# Minimal_carrier_board_for_CM4_rev_A.net
KiCad netlist of a schematic drawn in EAGLE
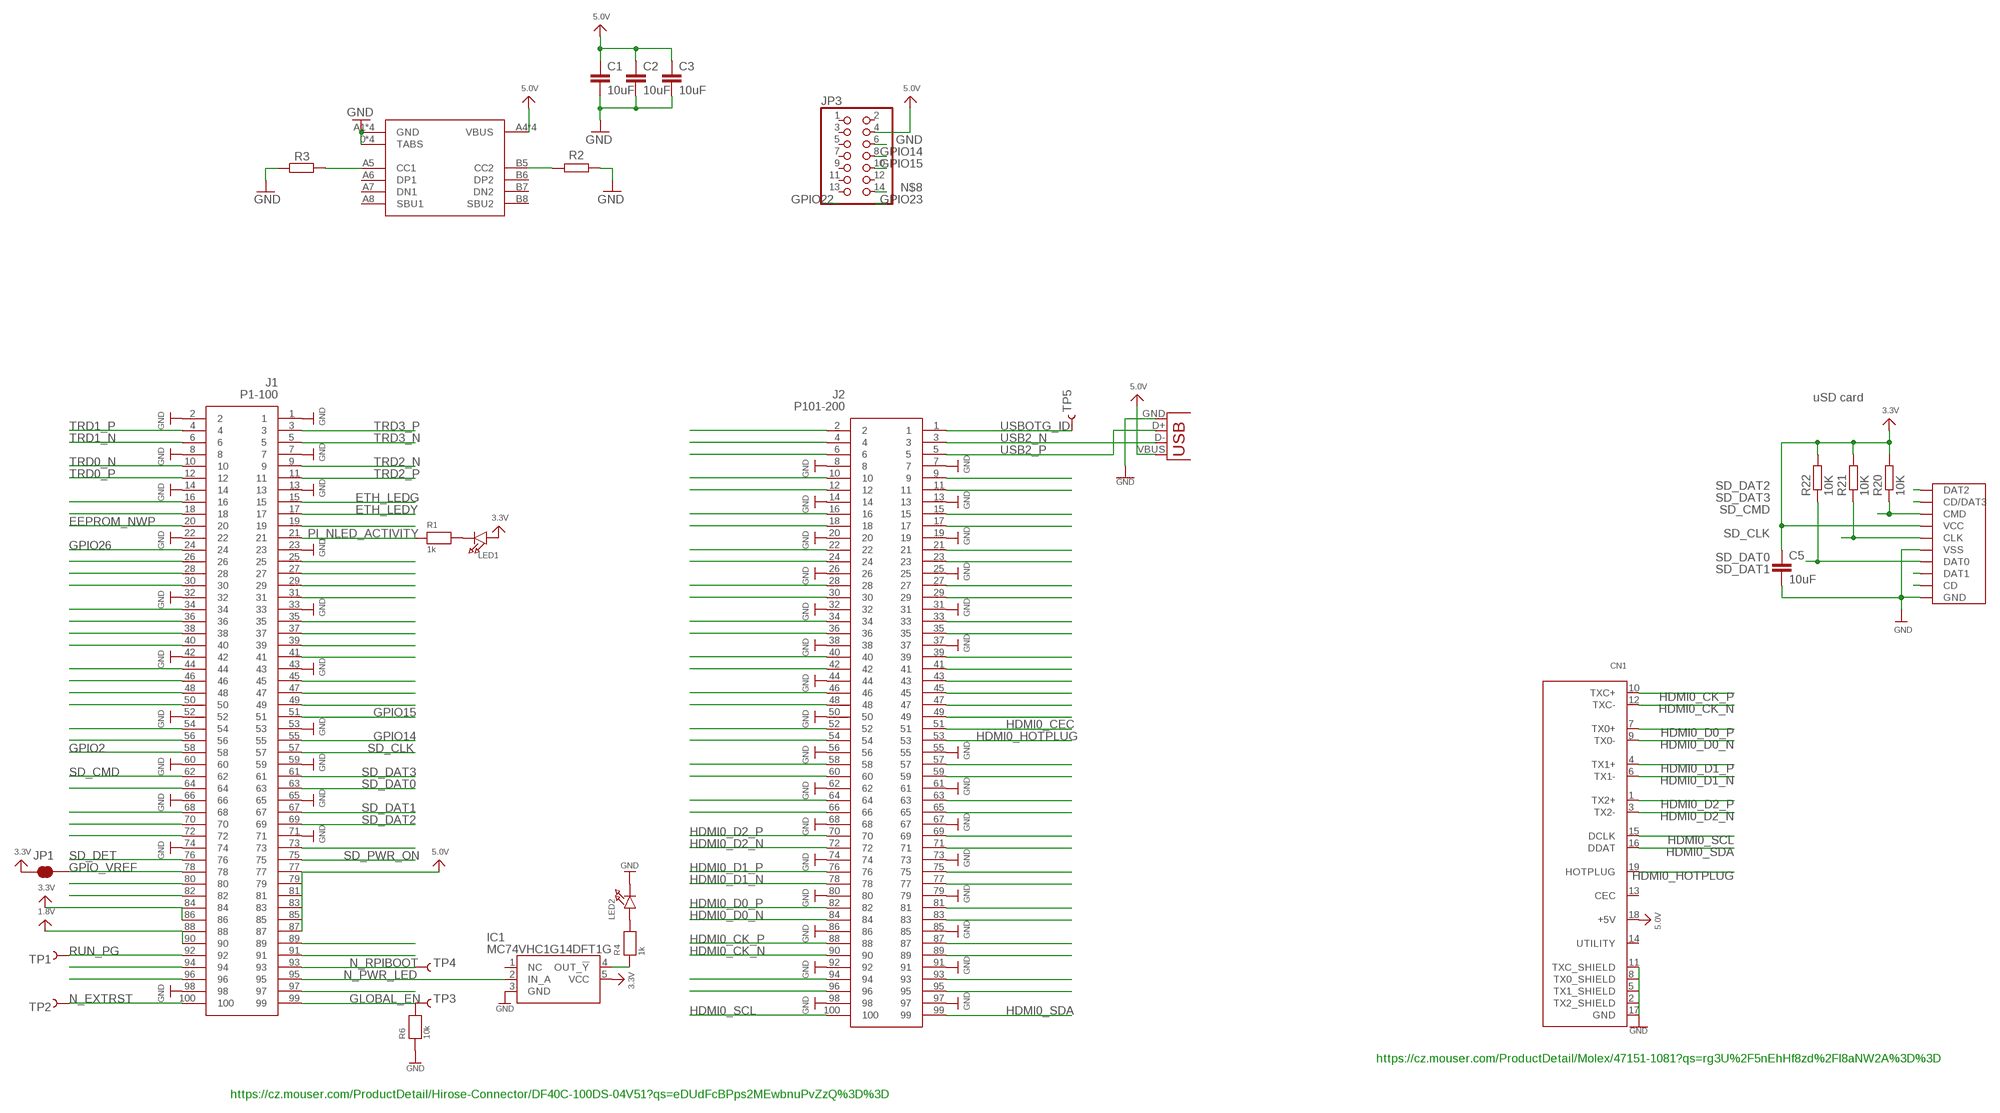
[diagram p0: schematic, sheet 1]

(export (version "E")
  (design (tool "Eeschema 10.0.6"))
  (components
    (comp (ref "C1")
      (value "10uF")
      (footprint "eagle-import:C0805")
      (libsource (lib "eagle-import") (part "C-EUC0805"))
    )
    (comp (ref "C2")
      (value "10uF")
      (footprint "eagle-import:C0805")
      (libsource (lib "eagle-import") (part "C-EUC0805"))
    )
    (comp (ref "C3")
      (value "10uF")
      (footprint "eagle-import:C0805")
      (libsource (lib "eagle-import") (part "C-EUC0805"))
    )
    (comp (ref "C5")
      (value "10uF")
      (footprint "eagle-import:C0805")
      (libsource (lib "eagle-import") (part "C-EUC0805"))
    )
    (comp (ref "CN1")
      (value "HDMI_MOLEX_47151-0001")
      (footprint "eagle-import:HDMI_MOLEX_47151-0001")
      (libsource (lib "eagle-import") (part "HDMI_MOLEX_47151-0001"))
    )
    (comp (ref "IC1")
      (value "MC74VHC1G14DFT1G")
      (footprint "eagle-import:SOT65P210X110-5N")
      (fields (field (name "MOUSER_PART_NUMBER") "863-MC74VHC1G14DFT1G"))
      (libsource (lib "eagle-import") (part "MC74VHC1G14DFT1G"))
    )
    (comp (ref "J1")
      (value "P1-100")
      (footprint "eagle-import:DF40C100DS04V51")
      (fields
        (field (name "MANUFACTURER_PART_NUMBER") "DF40C-100DS-0.4V(51)")
        (field (name "MOUSER_PART_NUMBER") "798-DF40C100DS0.4V51")
      )
      (libsource (lib "eagle-import") (part "DF40C-100DS-0.4V_51_"))
    )
    (comp (ref "J2")
      (value "P101-200")
      (footprint "eagle-import:DF40C100DS04V51")
      (fields
        (field (name "MANUFACTURER_PART_NUMBER") "DF40C-100DS-0.4V(51)")
        (field (name "MOUSER_PART_NUMBER") "798-DF40C100DS0.4V51")
      )
      (libsource (lib "eagle-import") (part "DF40C-100DS-0.4V_51_"))
    )
    (comp (ref "JP1")
      (value "JUMPER-SMT_2_NC_TRACE_NO-SILK")
      (footprint "eagle-import:SMT-JUMPER_2_NC_TRACE_NO-SILK")
      (libsource (lib "eagle-import") (part "JUMPER-SMT_2_NC_TRACE_NO-SILK"))
    )
    (comp (ref "JP3")
      (value "PINHD-2X7")
      (footprint "eagle-import:2X07")
      (libsource (lib "eagle-import") (part "PINHD-2X7"))
    )
    (comp (ref "LED1")
      (value "LED0805_NOOUTLINE")
      (footprint "eagle-import:CHIPLED_0805_NOOUTLINE")
      (libsource (lib "eagle-import") (part "LED0805_NOOUTLINE"))
    )
    (comp (ref "LED2")
      (value "LED0805_NOOUTLINE")
      (footprint "eagle-import:CHIPLED_0805_NOOUTLINE")
      (libsource (lib "eagle-import") (part "LED0805_NOOUTLINE"))
    )
    (comp (ref "R1")
      (value "1k")
      (footprint "eagle-import:_0805MP")
      (libsource (lib "eagle-import") (part "RESISTOR_0805MP"))
    )
    (comp (ref "R2")
      (value "5.1k")
      (footprint "eagle-import:R0805")
      (libsource (lib "eagle-import") (part "R-EU_R0805"))
    )
    (comp (ref "R3")
      (value "5.1k")
      (footprint "eagle-import:R0805")
      (libsource (lib "eagle-import") (part "R-EU_R0805"))
    )
    (comp (ref "R4")
      (value "1k")
      (footprint "eagle-import:_0805MP")
      (libsource (lib "eagle-import") (part "RESISTOR_0805MP"))
    )
    (comp (ref "R6")
      (value "10k")
      (footprint "eagle-import:_0805MP")
      (libsource (lib "eagle-import") (part "RESISTOR_0805MP"))
    )
    (comp (ref "R20")
      (value "10K")
      (footprint "eagle-import:R0805")
      (libsource (lib "eagle-import") (part "R-EU_R0805"))
    )
    (comp (ref "R21")
      (value "10K")
      (footprint "eagle-import:R0805")
      (libsource (lib "eagle-import") (part "R-EU_R0805"))
    )
    (comp (ref "R22")
      (value "10K")
      (footprint "eagle-import:R0805")
      (libsource (lib "eagle-import") (part "R-EU_R0805"))
    )
    (comp (ref "SD_CARD")
      (value "MICRO_SD_CARD_")
      (footprint "eagle-import:TFP09-2--12B")
      (libsource (lib "eagle-import") (part "MICRO_SD_CARD_"))
    )
    (comp (ref "TP1")
      (value "TEST-POINT3X5")
      (footprint "eagle-import:PAD.03X.05")
      (libsource (lib "eagle-import") (part "TEST-POINT3X5"))
    )
    (comp (ref "TP2")
      (value "TEST-POINT3X5")
      (footprint "eagle-import:PAD.03X.05")
      (libsource (lib "eagle-import") (part "TEST-POINT3X5"))
    )
    (comp (ref "TP3")
      (value "TEST-POINT3X5")
      (footprint "eagle-import:PAD.03X.05")
      (libsource (lib "eagle-import") (part "TEST-POINT3X5"))
    )
    (comp (ref "TP4")
      (value "TEST-POINT3X5")
      (footprint "eagle-import:PAD.03X.05")
      (libsource (lib "eagle-import") (part "TEST-POINT3X5"))
    )
    (comp (ref "TP5")
      (value "TEST-POINT3X5")
      (footprint "eagle-import:PAD.03X.05")
      (libsource (lib "eagle-import") (part "TEST-POINT3X5"))
    )
    (comp (ref "U$59")
      (value "TYPE-C-31-M-12")
      (footprint "eagle-import:USB-TYPE-C_16PIN-MALE-TYPE-C-31-M-12")
      (libsource (lib "eagle-import") (part "TYPE-C-31-M-12"))
    )
    (comp (ref "USB2")
      (value "USBA-PTH")
      (footprint "eagle-import:USB-A-F-PTH")
      (libsource (lib "eagle-import") (part "USBA-PTH"))
    )
  )
  (nets
    (net (code "1") (name "/EEPROM_NWP") (class "Default")
      (node (ref "J1") (pin "20") (pinfunction "20_20") (pintype "bidirectional"))
    )
    (net (code "2") (name "/ETH_LEDG") (class "Default")
      (node (ref "J1") (pin "15") (pinfunction "15_15") (pintype "bidirectional"))
    )
    (net (code "3") (name "/ETH_LEDY") (class "Default")
      (node (ref "J1") (pin "17") (pinfunction "17_17") (pintype "bidirectional"))
    )
    (net (code "4") (name "/GLOBAL_EN") (class "Default")
      (node (ref "J1") (pin "99") (pinfunction "99_99") (pintype "bidirectional"))
      (node (ref "R6") (pin "2") (pinfunction "2_2") (pintype "passive"))
      (node (ref "TP3") (pin "P$1") (pinfunction "1_P$1") (pintype "bidirectional"))
    )
    (net (code "5") (name "/GPIO2") (class "Default")
      (node (ref "J1") (pin "58") (pinfunction "58_58") (pintype "bidirectional"))
    )
    (net (code "6") (name "/GPIO14") (class "Default")
      (node (ref "J1") (pin "55") (pinfunction "55_55") (pintype "bidirectional"))
      (node (ref "JP3") (pin "8") (pinfunction "8_8") (pintype "passive"))
    )
    (net (code "7") (name "/GPIO15") (class "Default")
      (node (ref "J1") (pin "51") (pinfunction "51_51") (pintype "bidirectional"))
      (node (ref "JP3") (pin "10") (pinfunction "10_10") (pintype "passive"))
    )
    (net (code "10") (name "/GPIO26") (class "Default")
      (node (ref "J1") (pin "24") (pinfunction "24_24") (pintype "bidirectional"))
    )
    (net (code "11") (name "/GPIO_VREF") (class "Default")
      (node (ref "J1") (pin "78") (pinfunction "78_78") (pintype "bidirectional"))
      (node (ref "JP1") (pin "2") (pinfunction "2_2") (pintype "passive"))
    )
    (net (code "12") (name "/HDMI0_CEC") (class "Default")
      (node (ref "J2") (pin "51") (pinfunction "51_51") (pintype "bidirectional"))
    )
    (net (code "13") (name "/HDMI0_CK_N") (class "Default")
      (node (ref "CN1") (pin "12") (pinfunction "TXC-_12") (pintype "bidirectional"))
      (node (ref "J2") (pin "90") (pinfunction "90_90") (pintype "bidirectional"))
    )
    (net (code "14") (name "/HDMI0_CK_P") (class "Default")
      (node (ref "CN1") (pin "10") (pinfunction "TXC+_10") (pintype "bidirectional"))
      (node (ref "J2") (pin "88") (pinfunction "88_88") (pintype "bidirectional"))
    )
    (net (code "15") (name "/HDMI0_D0_N") (class "Default")
      (node (ref "CN1") (pin "9") (pinfunction "TX0-_9") (pintype "bidirectional"))
      (node (ref "J2") (pin "84") (pinfunction "84_84") (pintype "bidirectional"))
    )
    (net (code "16") (name "/HDMI0_D0_P") (class "Default")
      (node (ref "CN1") (pin "7") (pinfunction "TX0+_7") (pintype "bidirectional"))
      (node (ref "J2") (pin "82") (pinfunction "82_82") (pintype "bidirectional"))
    )
    (net (code "17") (name "/HDMI0_D1_N") (class "Default")
      (node (ref "CN1") (pin "6") (pinfunction "TX1-_6") (pintype "bidirectional"))
      (node (ref "J2") (pin "78") (pinfunction "78_78") (pintype "bidirectional"))
    )
    (net (code "18") (name "/HDMI0_D1_P") (class "Default")
      (node (ref "CN1") (pin "4") (pinfunction "TX1+_4") (pintype "bidirectional"))
      (node (ref "J2") (pin "76") (pinfunction "76_76") (pintype "bidirectional"))
    )
    (net (code "19") (name "/HDMI0_D2_N") (class "Default")
      (node (ref "CN1") (pin "3") (pinfunction "TX2-_3") (pintype "bidirectional"))
      (node (ref "J2") (pin "72") (pinfunction "72_72") (pintype "bidirectional"))
    )
    (net (code "20") (name "/HDMI0_D2_P") (class "Default")
      (node (ref "CN1") (pin "1") (pinfunction "TX2+_1") (pintype "bidirectional"))
      (node (ref "J2") (pin "70") (pinfunction "70_70") (pintype "bidirectional"))
    )
    (net (code "21") (name "/HDMI0_HOTPLUG") (class "Default")
      (node (ref "CN1") (pin "19") (pinfunction "HOTPLUG_19") (pintype "bidirectional"))
      (node (ref "J2") (pin "53") (pinfunction "53_53") (pintype "bidirectional"))
    )
    (net (code "22") (name "/HDMI0_SCL") (class "Default")
      (node (ref "CN1") (pin "15") (pinfunction "DCLK_15") (pintype "bidirectional"))
      (node (ref "J2") (pin "100") (pinfunction "100_100") (pintype "bidirectional"))
    )
    (net (code "23") (name "/HDMI0_SDA") (class "Default")
      (node (ref "CN1") (pin "16") (pinfunction "DDAT_16") (pintype "bidirectional"))
      (node (ref "J2") (pin "99") (pinfunction "99_99") (pintype "bidirectional"))
    )
    (net (code "24") (name "/N$8") (class "Default")
      (node (ref "JP3") (pin "14") (pinfunction "14_14") (pintype "passive"))
    )
    (net (code "25") (name "/N_EXTRST") (class "Default")
      (node (ref "J1") (pin "100") (pinfunction "100_100") (pintype "bidirectional"))
      (node (ref "TP2") (pin "P$1") (pinfunction "1_P$1") (pintype "bidirectional"))
    )
    (net (code "26") (name "/N_PWR_LED") (class "Default")
      (node (ref "IC1") (pin "2") (pinfunction "IN_A_2") (pintype "input"))
      (node (ref "J1") (pin "95") (pinfunction "95_95") (pintype "bidirectional"))
    )
    (net (code "27") (name "/N_RPIBOOT") (class "Default")
      (node (ref "J1") (pin "93") (pinfunction "93_93") (pintype "bidirectional"))
      (node (ref "TP4") (pin "P$1") (pinfunction "1_P$1") (pintype "bidirectional"))
    )
    (net (code "28") (name "/PI_NLED_ACTIVITY") (class "Default")
      (node (ref "J1") (pin "21") (pinfunction "21_21") (pintype "bidirectional"))
      (node (ref "R1") (pin "1") (pinfunction "1_1") (pintype "passive"))
    )
    (net (code "29") (name "/RUN_PG") (class "Default")
      (node (ref "J1") (pin "92") (pinfunction "92_92") (pintype "bidirectional"))
      (node (ref "TP1") (pin "P$1") (pinfunction "1_P$1") (pintype "bidirectional"))
    )
    (net (code "30") (name "/SD_CLK") (class "Default")
      (node (ref "J1") (pin "57") (pinfunction "57_57") (pintype "bidirectional"))
      (node (ref "R21") (pin "1") (pinfunction "1_1") (pintype "passive"))
      (node (ref "SD_CARD") (pin "CLK") (pinfunction "CLK_CLK") (pintype "bidirectional"))
    )
    (net (code "31") (name "/SD_CMD") (class "Default")
      (node (ref "J1") (pin "62") (pinfunction "62_62") (pintype "bidirectional"))
      (node (ref "R20") (pin "1") (pinfunction "1_1") (pintype "passive"))
      (node (ref "SD_CARD") (pin "CMD") (pinfunction "CMD_CMD") (pintype "bidirectional"))
    )
    (net (code "32") (name "/SD_DAT0") (class "Default")
      (node (ref "J1") (pin "63") (pinfunction "63_63") (pintype "bidirectional"))
      (node (ref "R22") (pin "1") (pinfunction "1_1") (pintype "passive"))
      (node (ref "SD_CARD") (pin "DAT0") (pinfunction "DAT0_DAT0") (pintype "bidirectional"))
    )
    (net (code "33") (name "/SD_DAT1") (class "Default")
      (node (ref "J1") (pin "67") (pinfunction "67_67") (pintype "bidirectional"))
      (node (ref "SD_CARD") (pin "DAT1") (pinfunction "DAT1_DAT1") (pintype "bidirectional"))
    )
    (net (code "34") (name "/SD_DAT2") (class "Default")
      (node (ref "J1") (pin "69") (pinfunction "69_69") (pintype "bidirectional"))
      (node (ref "SD_CARD") (pin "DAT2") (pinfunction "DAT2_DAT2") (pintype "bidirectional"))
    )
    (net (code "35") (name "/SD_DAT3") (class "Default")
      (node (ref "J1") (pin "61") (pinfunction "61_61") (pintype "bidirectional"))
      (node (ref "SD_CARD") (pin "CD/DAT3") (pinfunction "CD/DAT3_CD/DAT3") (pintype "bidirectional"))
    )
    (net (code "36") (name "/SD_DET") (class "Default")
      (node (ref "J1") (pin "76") (pinfunction "76_76") (pintype "bidirectional"))
    )
    (net (code "37") (name "/SD_PWR_ON") (class "Default")
      (node (ref "J1") (pin "75") (pinfunction "75_75") (pintype "bidirectional"))
    )
    (net (code "38") (name "/TRD0_N") (class "Default")
      (node (ref "J1") (pin "10") (pinfunction "10_10") (pintype "bidirectional"))
    )
    (net (code "39") (name "/TRD0_P") (class "Default")
      (node (ref "J1") (pin "12") (pinfunction "12_12") (pintype "bidirectional"))
    )
    (net (code "40") (name "/TRD1_N") (class "Default")
      (node (ref "J1") (pin "6") (pinfunction "6_6") (pintype "bidirectional"))
    )
    (net (code "41") (name "/TRD1_P") (class "Default")
      (node (ref "J1") (pin "4") (pinfunction "4_4") (pintype "bidirectional"))
    )
    (net (code "42") (name "/TRD2_N") (class "Default")
      (node (ref "J1") (pin "9") (pinfunction "9_9") (pintype "bidirectional"))
    )
    (net (code "43") (name "/TRD2_P") (class "Default")
      (node (ref "J1") (pin "11") (pinfunction "11_11") (pintype "bidirectional"))
    )
    (net (code "44") (name "/TRD3_N") (class "Default")
      (node (ref "J1") (pin "5") (pinfunction "5_5") (pintype "bidirectional"))
    )
    (net (code "45") (name "/TRD3_P") (class "Default")
      (node (ref "J1") (pin "3") (pinfunction "3_3") (pintype "bidirectional"))
    )
    (net (code "46") (name "/USB2_N") (class "Default")
      (node (ref "J2") (pin "3") (pinfunction "3_3") (pintype "bidirectional"))
      (node (ref "USB2") (pin "D-") (pinfunction "D-_D-") (pintype "bidirectional"))
    )
    (net (code "47") (name "/USB2_P") (class "Default")
      (node (ref "J2") (pin "5") (pinfunction "5_5") (pintype "bidirectional"))
      (node (ref "USB2") (pin "D+") (pinfunction "D+_D+") (pintype "bidirectional"))
    )
    (net (code "48") (name "/USBOTG_ID") (class "Default")
      (node (ref "J2") (pin "1") (pinfunction "1_1") (pintype "bidirectional"))
      (node (ref "TP5") (pin "P$1") (pinfunction "1_P$1") (pintype "bidirectional"))
    )
    (net (code "49") (name "1.8V") (class "Default")
      (node (ref "J1") (pin "88") (pinfunction "88_88") (pintype "bidirectional"))
      (node (ref "J1") (pin "90") (pinfunction "90_90") (pintype "bidirectional"))
    )
    (net (code "50") (name "3.3V") (class "Default")
      (node (ref "C5") (pin "1") (pinfunction "1_1") (pintype "passive"))
      (node (ref "IC1") (pin "5") (pinfunction "VCC_5") (pintype "power_in"))
      (node (ref "J1") (pin "84") (pinfunction "84_84") (pintype "bidirectional"))
      (node (ref "J1") (pin "86") (pinfunction "86_86") (pintype "bidirectional"))
      (node (ref "JP1") (pin "1") (pinfunction "1_1") (pintype "passive"))
      (node (ref "LED1") (pin "A") (pinfunction "A_A") (pintype "passive"))
      (node (ref "R20") (pin "2") (pinfunction "2_2") (pintype "passive"))
      (node (ref "R21") (pin "2") (pinfunction "2_2") (pintype "passive"))
      (node (ref "R22") (pin "2") (pinfunction "2_2") (pintype "passive"))
      (node (ref "SD_CARD") (pin "VCC") (pinfunction "VCC_VCC") (pintype "bidirectional"))
    )
    (net (code "51") (name "5.0V") (class "Default")
      (node (ref "C1") (pin "1") (pinfunction "1_1") (pintype "passive"))
      (node (ref "C2") (pin "1") (pinfunction "1_1") (pintype "passive"))
      (node (ref "C3") (pin "1") (pinfunction "1_1") (pintype "passive"))
      (node (ref "CN1") (pin "18") (pinfunction "+5V_18") (pintype "power_in"))
      (node (ref "J1") (pin "77") (pinfunction "77_77") (pintype "bidirectional"))
      (node (ref "J1") (pin "79") (pinfunction "79_79") (pintype "bidirectional"))
      (node (ref "J1") (pin "81") (pinfunction "81_81") (pintype "bidirectional"))
      (node (ref "J1") (pin "83") (pinfunction "83_83") (pintype "bidirectional"))
      (node (ref "J1") (pin "85") (pinfunction "85_85") (pintype "bidirectional"))
      (node (ref "J1") (pin "87") (pinfunction "87_87") (pintype "bidirectional"))
      (node (ref "JP3") (pin "4") (pinfunction "4_4") (pintype "passive"))
      (node (ref "U$59") (pin "A4") (pinfunction "VBUS_A4") (pintype "bidirectional"))
      (node (ref "U$59") (pin "A9") (pinfunction "VBUS_A9") (pintype "bidirectional"))
      (node (ref "U$59") (pin "B4") (pinfunction "VBUS_B4") (pintype "bidirectional"))
      (node (ref "U$59") (pin "B9") (pinfunction "VBUS_B9") (pintype "bidirectional"))
      (node (ref "USB2") (pin "VBUS") (pinfunction "VBUS_VBUS") (pintype "bidirectional"))
    )
    (net (code "52") (name "GND") (class "Default")
      (node (ref "C1") (pin "2") (pinfunction "2_2") (pintype "passive"))
      (node (ref "C2") (pin "2") (pinfunction "2_2") (pintype "passive"))
      (node (ref "C3") (pin "2") (pinfunction "2_2") (pintype "passive"))
      (node (ref "C5") (pin "2") (pinfunction "2_2") (pintype "passive"))
      (node (ref "CN1") (pin "11") (pinfunction "TXC_SHIELD_11") (pintype "power_in"))
      (node (ref "CN1") (pin "17") (pinfunction "GND_17") (pintype "power_in"))
      (node (ref "CN1") (pin "2") (pinfunction "TX2_SHIELD_2") (pintype "power_in"))
      (node (ref "CN1") (pin "5") (pinfunction "TX1_SHIELD_5") (pintype "power_in"))
      (node (ref "CN1") (pin "8") (pinfunction "TX0_SHIELD_8") (pintype "power_in"))
      (node (ref "IC1") (pin "3") (pinfunction "GND_3") (pintype "power_in"))
      (node (ref "J1") (pin "1") (pinfunction "1_1") (pintype "bidirectional"))
      (node (ref "J1") (pin "13") (pinfunction "13_13") (pintype "bidirectional"))
      (node (ref "J1") (pin "14") (pinfunction "14_14") (pintype "bidirectional"))
      (node (ref "J1") (pin "2") (pinfunction "2_2") (pintype "bidirectional"))
      (node (ref "J1") (pin "22") (pinfunction "22_22") (pintype "bidirectional"))
      (node (ref "J1") (pin "23") (pinfunction "23_23") (pintype "bidirectional"))
      (node (ref "J1") (pin "32") (pinfunction "32_32") (pintype "bidirectional"))
      (node (ref "J1") (pin "33") (pinfunction "33_33") (pintype "bidirectional"))
      (node (ref "J1") (pin "42") (pinfunction "42_42") (pintype "bidirectional"))
      (node (ref "J1") (pin "43") (pinfunction "43_43") (pintype "bidirectional"))
      (node (ref "J1") (pin "52") (pinfunction "52_52") (pintype "bidirectional"))
      (node (ref "J1") (pin "53") (pinfunction "53_53") (pintype "bidirectional"))
      (node (ref "J1") (pin "59") (pinfunction "59_59") (pintype "bidirectional"))
      (node (ref "J1") (pin "60") (pinfunction "60_60") (pintype "bidirectional"))
      (node (ref "J1") (pin "65") (pinfunction "65_65") (pintype "bidirectional"))
      (node (ref "J1") (pin "66") (pinfunction "66_66") (pintype "bidirectional"))
      (node (ref "J1") (pin "7") (pinfunction "7_7") (pintype "bidirectional"))
      (node (ref "J1") (pin "71") (pinfunction "71_71") (pintype "bidirectional"))
      (node (ref "J1") (pin "74") (pinfunction "74_74") (pintype "bidirectional"))
      (node (ref "J1") (pin "8") (pinfunction "8_8") (pintype "bidirectional"))
      (node (ref "J1") (pin "98") (pinfunction "98_98") (pintype "bidirectional"))
      (node (ref "J2") (pin "13") (pinfunction "13_13") (pintype "bidirectional"))
      (node (ref "J2") (pin "14") (pinfunction "14_14") (pintype "bidirectional"))
      (node (ref "J2") (pin "19") (pinfunction "19_19") (pintype "bidirectional"))
      (node (ref "J2") (pin "20") (pinfunction "20_20") (pintype "bidirectional"))
      (node (ref "J2") (pin "25") (pinfunction "25_25") (pintype "bidirectional"))
      (node (ref "J2") (pin "26") (pinfunction "26_26") (pintype "bidirectional"))
      (node (ref "J2") (pin "31") (pinfunction "31_31") (pintype "bidirectional"))
      (node (ref "J2") (pin "32") (pinfunction "32_32") (pintype "bidirectional"))
      (node (ref "J2") (pin "37") (pinfunction "37_37") (pintype "bidirectional"))
      (node (ref "J2") (pin "38") (pinfunction "38_38") (pintype "bidirectional"))
      (node (ref "J2") (pin "44") (pinfunction "44_44") (pintype "bidirectional"))
      (node (ref "J2") (pin "50") (pinfunction "50_50") (pintype "bidirectional"))
      (node (ref "J2") (pin "55") (pinfunction "55_55") (pintype "bidirectional"))
      (node (ref "J2") (pin "56") (pinfunction "56_56") (pintype "bidirectional"))
      (node (ref "J2") (pin "61") (pinfunction "61_61") (pintype "bidirectional"))
      (node (ref "J2") (pin "62") (pinfunction "62_62") (pintype "bidirectional"))
      (node (ref "J2") (pin "67") (pinfunction "67_67") (pintype "bidirectional"))
      (node (ref "J2") (pin "68") (pinfunction "68_68") (pintype "bidirectional"))
      (node (ref "J2") (pin "7") (pinfunction "7_7") (pintype "bidirectional"))
      (node (ref "J2") (pin "73") (pinfunction "73_73") (pintype "bidirectional"))
      (node (ref "J2") (pin "74") (pinfunction "74_74") (pintype "bidirectional"))
      (node (ref "J2") (pin "79") (pinfunction "79_79") (pintype "bidirectional"))
      (node (ref "J2") (pin "8") (pinfunction "8_8") (pintype "bidirectional"))
      (node (ref "J2") (pin "80") (pinfunction "80_80") (pintype "bidirectional"))
      (node (ref "J2") (pin "85") (pinfunction "85_85") (pintype "bidirectional"))
      (node (ref "J2") (pin "86") (pinfunction "86_86") (pintype "bidirectional"))
      (node (ref "J2") (pin "91") (pinfunction "91_91") (pintype "bidirectional"))
      (node (ref "J2") (pin "92") (pinfunction "92_92") (pintype "bidirectional"))
      (node (ref "J2") (pin "97") (pinfunction "97_97") (pintype "bidirectional"))
      (node (ref "J2") (pin "98") (pinfunction "98_98") (pintype "bidirectional"))
      (node (ref "JP3") (pin "6") (pinfunction "6_6") (pintype "passive"))
      (node (ref "LED2") (pin "C") (pinfunction "C_C") (pintype "passive"))
      (node (ref "R2") (pin "2") (pinfunction "2_2") (pintype "passive"))
      (node (ref "R3") (pin "1") (pinfunction "1_1") (pintype "passive"))
      (node (ref "R6") (pin "1") (pinfunction "1_1") (pintype "passive"))
      (node (ref "SD_CARD") (pin "GND") (pinfunction "GND_GND") (pintype "bidirectional"))
      (node (ref "SD_CARD") (pin "GND@1") (pinfunction "GND_GND@1") (pintype "bidirectional"))
      (node (ref "SD_CARD") (pin "GND@2") (pinfunction "GND_GND@2") (pintype "bidirectional"))
      (node (ref "SD_CARD") (pin "GND@3") (pinfunction "VSS_GND@3") (pintype "bidirectional"))
      (node (ref "SD_CARD") (pin "VSS") (pinfunction "GND_VSS") (pintype "bidirectional"))
      (node (ref "U$59") (pin "0") (pinfunction "TABS_0") (pintype "bidirectional"))
      (node (ref "U$59") (pin "0-1") (pinfunction "TABS_0-1") (pintype "bidirectional"))
      (node (ref "U$59") (pin "0-2") (pinfunction "TABS_0-2") (pintype "bidirectional"))
      (node (ref "U$59") (pin "0-3") (pinfunction "TABS_0-3") (pintype "bidirectional"))
      (node (ref "U$59") (pin "A1") (pinfunction "GND_A1") (pintype "bidirectional"))
      (node (ref "U$59") (pin "A12") (pinfunction "GND_A12") (pintype "bidirectional"))
      (node (ref "U$59") (pin "B1") (pinfunction "GND_B1") (pintype "bidirectional"))
      (node (ref "U$59") (pin "B12") (pinfunction "GND_B12") (pintype "bidirectional"))
      (node (ref "USB2") (pin "GND") (pinfunction "GND_GND") (pintype "bidirectional"))
    )
    (net (code "53") (name "Net-(IC1-OUT_~{Y})") (class "Default")
      (node (ref "IC1") (pin "4") (pinfunction "OUT_~{Y}_4") (pintype "output"))
      (node (ref "R4") (pin "1") (pinfunction "1_1") (pintype "passive"))
    )
    (net (code "54") (name "Net-(LED1-PadC)") (class "Default")
      (node (ref "LED1") (pin "C") (pinfunction "C_C") (pintype "passive"))
      (node (ref "R1") (pin "2") (pinfunction "2_2") (pintype "passive"))
    )
    (net (code "55") (name "Net-(LED2-PadA)") (class "Default")
      (node (ref "LED2") (pin "A") (pinfunction "A_A") (pintype "passive"))
      (node (ref "R4") (pin "2") (pinfunction "2_2") (pintype "passive"))
    )
    (net (code "56") (name "Net-(U$59-CC1)") (class "Default")
      (node (ref "R3") (pin "2") (pinfunction "2_2") (pintype "passive"))
      (node (ref "U$59") (pin "A5") (pinfunction "CC1_A5") (pintype "bidirectional"))
    )
    (net (code "57") (name "Net-(U$59-CC2)") (class "Default")
      (node (ref "R2") (pin "1") (pinfunction "1_1") (pintype "passive"))
      (node (ref "U$59") (pin "B5") (pinfunction "CC2_B5") (pintype "bidirectional"))
    )
    (net (code "58") (name "unconnected-(CN1A-CEC-Pad13)") (class "Default")
      (node (ref "CN1") (pin "13") (pinfunction "CEC_13") (pintype "bidirectional"))
    )
    (net (code "59") (name "unconnected-(CN1A-UTILITY-Pad14)") (class "Default")
      (node (ref "CN1") (pin "14") (pinfunction "UTILITY_14") (pintype "bidirectional"))
    )
    (net (code "60") (name "unconnected-(IC1-NC-Pad1)") (class "Default")
      (node (ref "IC1") (pin "1") (pinfunction "NC_1") (pintype "no_connect"))
    )
    (net (code "61") (name "unconnected-(J1-Pad16)") (class "Default")
      (node (ref "J1") (pin "16") (pinfunction "16_16") (pintype "bidirectional"))
    )
    (net (code "62") (name "unconnected-(J1-Pad18)") (class "Default")
      (node (ref "J1") (pin "18") (pinfunction "18_18") (pintype "bidirectional"))
    )
    (net (code "63") (name "unconnected-(J1-Pad19)") (class "Default")
      (node (ref "J1") (pin "19") (pinfunction "19_19") (pintype "bidirectional"))
    )
    (net (code "64") (name "unconnected-(J1-Pad25)") (class "Default")
      (node (ref "J1") (pin "25") (pinfunction "25_25") (pintype "bidirectional"))
    )
    (net (code "65") (name "unconnected-(J1-Pad26)") (class "Default")
      (node (ref "J1") (pin "26") (pinfunction "26_26") (pintype "bidirectional"))
    )
    (net (code "66") (name "unconnected-(J1-Pad27)") (class "Default")
      (node (ref "J1") (pin "27") (pinfunction "27_27") (pintype "bidirectional"))
    )
    (net (code "67") (name "unconnected-(J1-Pad28)") (class "Default")
      (node (ref "J1") (pin "28") (pinfunction "28_28") (pintype "bidirectional"))
    )
    (net (code "68") (name "unconnected-(J1-Pad29)") (class "Default")
      (node (ref "J1") (pin "29") (pinfunction "29_29") (pintype "bidirectional"))
    )
    (net (code "69") (name "unconnected-(J1-Pad30)") (class "Default")
      (node (ref "J1") (pin "30") (pinfunction "30_30") (pintype "bidirectional"))
    )
    (net (code "70") (name "unconnected-(J1-Pad31)") (class "Default")
      (node (ref "J1") (pin "31") (pinfunction "31_31") (pintype "bidirectional"))
    )
    (net (code "71") (name "unconnected-(J1-Pad34)") (class "Default")
      (node (ref "J1") (pin "34") (pinfunction "34_34") (pintype "bidirectional"))
    )
    (net (code "72") (name "unconnected-(J1-Pad35)") (class "Default")
      (node (ref "J1") (pin "35") (pinfunction "35_35") (pintype "bidirectional"))
    )
    (net (code "73") (name "unconnected-(J1-Pad36)") (class "Default")
      (node (ref "J1") (pin "36") (pinfunction "36_36") (pintype "bidirectional"))
    )
    (net (code "74") (name "unconnected-(J1-Pad37)") (class "Default")
      (node (ref "J1") (pin "37") (pinfunction "37_37") (pintype "bidirectional"))
    )
    (net (code "75") (name "unconnected-(J1-Pad38)") (class "Default")
      (node (ref "J1") (pin "38") (pinfunction "38_38") (pintype "bidirectional"))
    )
    (net (code "76") (name "unconnected-(J1-Pad39)") (class "Default")
      (node (ref "J1") (pin "39") (pinfunction "39_39") (pintype "bidirectional"))
    )
    (net (code "77") (name "unconnected-(J1-Pad40)") (class "Default")
      (node (ref "J1") (pin "40") (pinfunction "40_40") (pintype "bidirectional"))
    )
    (net (code "78") (name "unconnected-(J1-Pad41)") (class "Default")
      (node (ref "J1") (pin "41") (pinfunction "41_41") (pintype "bidirectional"))
    )
    (net (code "79") (name "unconnected-(J1-Pad44)") (class "Default")
      (node (ref "J1") (pin "44") (pinfunction "44_44") (pintype "bidirectional"))
    )
    (net (code "80") (name "unconnected-(J1-Pad45)") (class "Default")
      (node (ref "J1") (pin "45") (pinfunction "45_45") (pintype "bidirectional"))
    )
    (net (code "81") (name "unconnected-(J1-Pad46)") (class "Default")
      (node (ref "J1") (pin "46") (pinfunction "46_46") (pintype "bidirectional"))
    )
    (net (code "82") (name "unconnected-(J1-Pad47)") (class "Default")
      (node (ref "J1") (pin "47") (pinfunction "47_47") (pintype "bidirectional"))
    )
    (net (code "83") (name "unconnected-(J1-Pad48)") (class "Default")
      (node (ref "J1") (pin "48") (pinfunction "48_48") (pintype "bidirectional"))
    )
    (net (code "84") (name "unconnected-(J1-Pad49)") (class "Default")
      (node (ref "J1") (pin "49") (pinfunction "49_49") (pintype "bidirectional"))
    )
    (net (code "85") (name "unconnected-(J1-Pad50)") (class "Default")
      (node (ref "J1") (pin "50") (pinfunction "50_50") (pintype "bidirectional"))
    )
    (net (code "86") (name "unconnected-(J1-Pad54)") (class "Default")
      (node (ref "J1") (pin "54") (pinfunction "54_54") (pintype "bidirectional"))
    )
    (net (code "87") (name "unconnected-(J1-Pad56)") (class "Default")
      (node (ref "J1") (pin "56") (pinfunction "56_56") (pintype "bidirectional"))
    )
    (net (code "88") (name "unconnected-(J1-Pad64)") (class "Default")
      (node (ref "J1") (pin "64") (pinfunction "64_64") (pintype "bidirectional"))
    )
    (net (code "89") (name "unconnected-(J1-Pad68)") (class "Default")
      (node (ref "J1") (pin "68") (pinfunction "68_68") (pintype "bidirectional"))
    )
    (net (code "90") (name "unconnected-(J1-Pad70)") (class "Default")
      (node (ref "J1") (pin "70") (pinfunction "70_70") (pintype "bidirectional"))
    )
    (net (code "91") (name "unconnected-(J1-Pad72)") (class "Default")
      (node (ref "J1") (pin "72") (pinfunction "72_72") (pintype "bidirectional"))
    )
    (net (code "92") (name "unconnected-(J1-Pad73)") (class "Default")
      (node (ref "J1") (pin "73") (pinfunction "73_73") (pintype "bidirectional"))
    )
    (net (code "93") (name "unconnected-(J1-Pad80)") (class "Default")
      (node (ref "J1") (pin "80") (pinfunction "80_80") (pintype "bidirectional"))
    )
    (net (code "94") (name "unconnected-(J1-Pad82)") (class "Default")
      (node (ref "J1") (pin "82") (pinfunction "82_82") (pintype "bidirectional"))
    )
    (net (code "95") (name "unconnected-(J1-Pad89)") (class "Default")
      (node (ref "J1") (pin "89") (pinfunction "89_89") (pintype "bidirectional"))
    )
    (net (code "96") (name "unconnected-(J1-Pad91)") (class "Default")
      (node (ref "J1") (pin "91") (pinfunction "91_91") (pintype "bidirectional"))
    )
    (net (code "97") (name "unconnected-(J1-Pad94)") (class "Default")
      (node (ref "J1") (pin "94") (pinfunction "94_94") (pintype "bidirectional"))
    )
    (net (code "98") (name "unconnected-(J1-Pad96)") (class "Default")
      (node (ref "J1") (pin "96") (pinfunction "96_96") (pintype "bidirectional"))
    )
    (net (code "99") (name "unconnected-(J1-Pad97)") (class "Default")
      (node (ref "J1") (pin "97") (pinfunction "97_97") (pintype "bidirectional"))
    )
    (net (code "100") (name "unconnected-(J2-Pad2)") (class "Default")
      (node (ref "J2") (pin "2") (pinfunction "2_2") (pintype "bidirectional"))
    )
    (net (code "101") (name "unconnected-(J2-Pad4)") (class "Default")
      (node (ref "J2") (pin "4") (pinfunction "4_4") (pintype "bidirectional"))
    )
    (net (code "102") (name "unconnected-(J2-Pad6)") (class "Default")
      (node (ref "J2") (pin "6") (pinfunction "6_6") (pintype "bidirectional"))
    )
    (net (code "103") (name "unconnected-(J2-Pad9)") (class "Default")
      (node (ref "J2") (pin "9") (pinfunction "9_9") (pintype "bidirectional"))
    )
    (net (code "104") (name "unconnected-(J2-Pad10)") (class "Default")
      (node (ref "J2") (pin "10") (pinfunction "10_10") (pintype "bidirectional"))
    )
    (net (code "105") (name "unconnected-(J2-Pad11)") (class "Default")
      (node (ref "J2") (pin "11") (pinfunction "11_11") (pintype "bidirectional"))
    )
    (net (code "106") (name "unconnected-(J2-Pad12)") (class "Default")
      (node (ref "J2") (pin "12") (pinfunction "12_12") (pintype "bidirectional"))
    )
    (net (code "107") (name "unconnected-(J2-Pad15)") (class "Default")
      (node (ref "J2") (pin "15") (pinfunction "15_15") (pintype "bidirectional"))
    )
    (net (code "108") (name "unconnected-(J2-Pad16)") (class "Default")
      (node (ref "J2") (pin "16") (pinfunction "16_16") (pintype "bidirectional"))
    )
    (net (code "109") (name "unconnected-(J2-Pad17)") (class "Default")
      (node (ref "J2") (pin "17") (pinfunction "17_17") (pintype "bidirectional"))
    )
    (net (code "110") (name "unconnected-(J2-Pad18)") (class "Default")
      (node (ref "J2") (pin "18") (pinfunction "18_18") (pintype "bidirectional"))
    )
    (net (code "111") (name "unconnected-(J2-Pad21)") (class "Default")
      (node (ref "J2") (pin "21") (pinfunction "21_21") (pintype "bidirectional"))
    )
    (net (code "112") (name "unconnected-(J2-Pad22)") (class "Default")
      (node (ref "J2") (pin "22") (pinfunction "22_22") (pintype "bidirectional"))
    )
    (net (code "113") (name "unconnected-(J2-Pad23)") (class "Default")
      (node (ref "J2") (pin "23") (pinfunction "23_23") (pintype "bidirectional"))
    )
    (net (code "114") (name "unconnected-(J2-Pad24)") (class "Default")
      (node (ref "J2") (pin "24") (pinfunction "24_24") (pintype "bidirectional"))
    )
    (net (code "115") (name "unconnected-(J2-Pad27)") (class "Default")
      (node (ref "J2") (pin "27") (pinfunction "27_27") (pintype "bidirectional"))
    )
    (net (code "116") (name "unconnected-(J2-Pad28)") (class "Default")
      (node (ref "J2") (pin "28") (pinfunction "28_28") (pintype "bidirectional"))
    )
    (net (code "117") (name "unconnected-(J2-Pad29)") (class "Default")
      (node (ref "J2") (pin "29") (pinfunction "29_29") (pintype "bidirectional"))
    )
    (net (code "118") (name "unconnected-(J2-Pad30)") (class "Default")
      (node (ref "J2") (pin "30") (pinfunction "30_30") (pintype "bidirectional"))
    )
    (net (code "119") (name "unconnected-(J2-Pad33)") (class "Default")
      (node (ref "J2") (pin "33") (pinfunction "33_33") (pintype "bidirectional"))
    )
    (net (code "120") (name "unconnected-(J2-Pad34)") (class "Default")
      (node (ref "J2") (pin "34") (pinfunction "34_34") (pintype "bidirectional"))
    )
    (net (code "121") (name "unconnected-(J2-Pad35)") (class "Default")
      (node (ref "J2") (pin "35") (pinfunction "35_35") (pintype "bidirectional"))
    )
    (net (code "122") (name "unconnected-(J2-Pad36)") (class "Default")
      (node (ref "J2") (pin "36") (pinfunction "36_36") (pintype "bidirectional"))
    )
    (net (code "123") (name "unconnected-(J2-Pad39)") (class "Default")
      (node (ref "J2") (pin "39") (pinfunction "39_39") (pintype "bidirectional"))
    )
    (net (code "124") (name "unconnected-(J2-Pad40)") (class "Default")
      (node (ref "J2") (pin "40") (pinfunction "40_40") (pintype "bidirectional"))
    )
    (net (code "125") (name "unconnected-(J2-Pad41)") (class "Default")
      (node (ref "J2") (pin "41") (pinfunction "41_41") (pintype "bidirectional"))
    )
    (net (code "126") (name "unconnected-(J2-Pad42)") (class "Default")
      (node (ref "J2") (pin "42") (pinfunction "42_42") (pintype "bidirectional"))
    )
    (net (code "127") (name "unconnected-(J2-Pad43)") (class "Default")
      (node (ref "J2") (pin "43") (pinfunction "43_43") (pintype "bidirectional"))
    )
    (net (code "128") (name "unconnected-(J2-Pad45)") (class "Default")
      (node (ref "J2") (pin "45") (pinfunction "45_45") (pintype "bidirectional"))
    )
    (net (code "129") (name "unconnected-(J2-Pad46)") (class "Default")
      (node (ref "J2") (pin "46") (pinfunction "46_46") (pintype "bidirectional"))
    )
    (net (code "130") (name "unconnected-(J2-Pad47)") (class "Default")
      (node (ref "J2") (pin "47") (pinfunction "47_47") (pintype "bidirectional"))
    )
    (net (code "131") (name "unconnected-(J2-Pad48)") (class "Default")
      (node (ref "J2") (pin "48") (pinfunction "48_48") (pintype "bidirectional"))
    )
    (net (code "132") (name "unconnected-(J2-Pad49)") (class "Default")
      (node (ref "J2") (pin "49") (pinfunction "49_49") (pintype "bidirectional"))
    )
    (net (code "133") (name "unconnected-(J2-Pad52)") (class "Default")
      (node (ref "J2") (pin "52") (pinfunction "52_52") (pintype "bidirectional"))
    )
    (net (code "134") (name "unconnected-(J2-Pad54)") (class "Default")
      (node (ref "J2") (pin "54") (pinfunction "54_54") (pintype "bidirectional"))
    )
    (net (code "135") (name "unconnected-(J2-Pad57)") (class "Default")
      (node (ref "J2") (pin "57") (pinfunction "57_57") (pintype "bidirectional"))
    )
    (net (code "136") (name "unconnected-(J2-Pad58)") (class "Default")
      (node (ref "J2") (pin "58") (pinfunction "58_58") (pintype "bidirectional"))
    )
    (net (code "137") (name "unconnected-(J2-Pad59)") (class "Default")
      (node (ref "J2") (pin "59") (pinfunction "59_59") (pintype "bidirectional"))
    )
    (net (code "138") (name "unconnected-(J2-Pad60)") (class "Default")
      (node (ref "J2") (pin "60") (pinfunction "60_60") (pintype "bidirectional"))
    )
    (net (code "139") (name "unconnected-(J2-Pad63)") (class "Default")
      (node (ref "J2") (pin "63") (pinfunction "63_63") (pintype "bidirectional"))
    )
    (net (code "140") (name "unconnected-(J2-Pad64)") (class "Default")
      (node (ref "J2") (pin "64") (pinfunction "64_64") (pintype "bidirectional"))
    )
    (net (code "141") (name "unconnected-(J2-Pad65)") (class "Default")
      (node (ref "J2") (pin "65") (pinfunction "65_65") (pintype "bidirectional"))
    )
    (net (code "142") (name "unconnected-(J2-Pad66)") (class "Default")
      (node (ref "J2") (pin "66") (pinfunction "66_66") (pintype "bidirectional"))
    )
    (net (code "143") (name "unconnected-(J2-Pad69)") (class "Default")
      (node (ref "J2") (pin "69") (pinfunction "69_69") (pintype "bidirectional"))
    )
    (net (code "144") (name "unconnected-(J2-Pad71)") (class "Default")
      (node (ref "J2") (pin "71") (pinfunction "71_71") (pintype "bidirectional"))
    )
    (net (code "145") (name "unconnected-(J2-Pad75)") (class "Default")
      (node (ref "J2") (pin "75") (pinfunction "75_75") (pintype "bidirectional"))
    )
    (net (code "146") (name "unconnected-(J2-Pad77)") (class "Default")
      (node (ref "J2") (pin "77") (pinfunction "77_77") (pintype "bidirectional"))
    )
    (net (code "147") (name "unconnected-(J2-Pad81)") (class "Default")
      (node (ref "J2") (pin "81") (pinfunction "81_81") (pintype "bidirectional"))
    )
    (net (code "148") (name "unconnected-(J2-Pad83)") (class "Default")
      (node (ref "J2") (pin "83") (pinfunction "83_83") (pintype "bidirectional"))
    )
    (net (code "149") (name "unconnected-(J2-Pad87)") (class "Default")
      (node (ref "J2") (pin "87") (pinfunction "87_87") (pintype "bidirectional"))
    )
    (net (code "150") (name "unconnected-(J2-Pad89)") (class "Default")
      (node (ref "J2") (pin "89") (pinfunction "89_89") (pintype "bidirectional"))
    )
    (net (code "151") (name "unconnected-(J2-Pad93)") (class "Default")
      (node (ref "J2") (pin "93") (pinfunction "93_93") (pintype "bidirectional"))
    )
    (net (code "152") (name "unconnected-(J2-Pad94)") (class "Default")
      (node (ref "J2") (pin "94") (pinfunction "94_94") (pintype "bidirectional"))
    )
    (net (code "153") (name "unconnected-(J2-Pad95)") (class "Default")
      (node (ref "J2") (pin "95") (pinfunction "95_95") (pintype "bidirectional"))
    )
    (net (code "154") (name "unconnected-(J2-Pad96)") (class "Default")
      (node (ref "J2") (pin "96") (pinfunction "96_96") (pintype "bidirectional"))
    )
    (net (code "155") (name "unconnected-(JP3-Pad1)") (class "Default")
      (node (ref "JP3") (pin "1") (pinfunction "1_1") (pintype "passive"))
    )
    (net (code "156") (name "unconnected-(JP3-Pad2)") (class "Default")
      (node (ref "JP3") (pin "2") (pinfunction "2_2") (pintype "passive"))
    )
    (net (code "157") (name "unconnected-(JP3-Pad3)") (class "Default")
      (node (ref "JP3") (pin "3") (pinfunction "3_3") (pintype "passive"))
    )
    (net (code "158") (name "unconnected-(JP3-Pad5)") (class "Default")
      (node (ref "JP3") (pin "5") (pinfunction "5_5") (pintype "passive"))
    )
    (net (code "159") (name "unconnected-(JP3-Pad7)") (class "Default")
      (node (ref "JP3") (pin "7") (pinfunction "7_7") (pintype "passive"))
    )
    (net (code "160") (name "unconnected-(JP3-Pad9)") (class "Default")
      (node (ref "JP3") (pin "9") (pinfunction "9_9") (pintype "passive"))
    )
    (net (code "161") (name "unconnected-(JP3-Pad11)") (class "Default")
      (node (ref "JP3") (pin "11") (pinfunction "11_11") (pintype "passive"))
    )
    (net (code "162") (name "unconnected-(JP3-Pad12)") (class "Default")
      (node (ref "JP3") (pin "12") (pinfunction "12_12") (pintype "passive"))
    )
    (net (code "163") (name "unconnected-(JP3-Pad13)") (class "Default")
      (node (ref "JP3") (pin "13") (pinfunction "13_13") (pintype "passive"))
    )
    (net (code "164") (name "unconnected-(SD_CARD-PadCD)") (class "Default")
      (node (ref "SD_CARD") (pin "CD") (pinfunction "CD_CD") (pintype "bidirectional"))
    )
    (net (code "165") (name "unconnected-(U$59-DN1-PadA7)") (class "Default")
      (node (ref "U$59") (pin "A7") (pinfunction "DN1_A7") (pintype "bidirectional"))
    )
    (net (code "166") (name "unconnected-(U$59-DN2-PadB7)") (class "Default")
      (node (ref "U$59") (pin "B7") (pinfunction "DN2_B7") (pintype "bidirectional"))
    )
    (net (code "167") (name "unconnected-(U$59-DP1-PadA6)") (class "Default")
      (node (ref "U$59") (pin "A6") (pinfunction "DP1_A6") (pintype "bidirectional"))
    )
    (net (code "168") (name "unconnected-(U$59-DP2-PadB6)") (class "Default")
      (node (ref "U$59") (pin "B6") (pinfunction "DP2_B6") (pintype "bidirectional"))
    )
    (net (code "169") (name "unconnected-(U$59-SBU1-PadA8)") (class "Default")
      (node (ref "U$59") (pin "A8") (pinfunction "SBU1_A8") (pintype "bidirectional"))
    )
    (net (code "170") (name "unconnected-(U$59-SBU2-PadB8)") (class "Default")
      (node (ref "U$59") (pin "B8") (pinfunction "SBU2_B8") (pintype "bidirectional"))
    )
  )
)
